# cap_meter.net
KiCad netlist of a schematic drawn in EAGLE
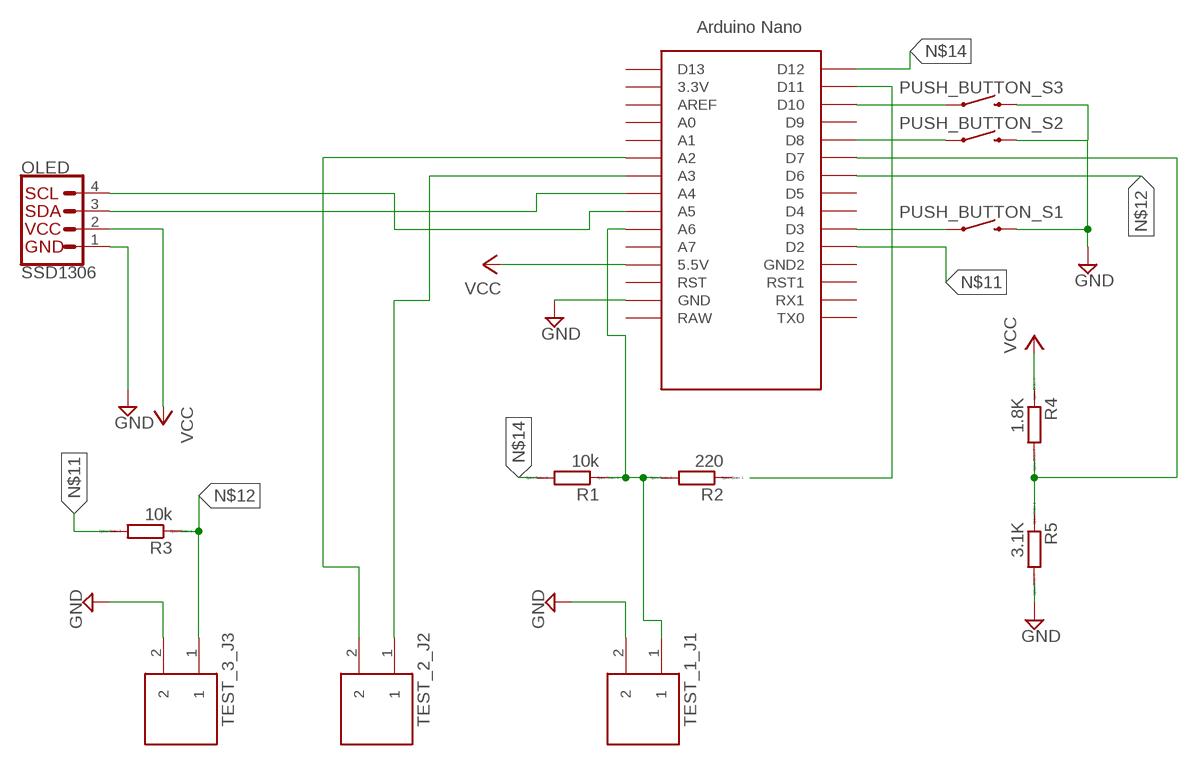
[diagram p0: schematic, sheet 1]

(export (version "E")
  (design (tool "Eeschema 10.0.6"))
  (components
    (comp (ref "OLED")
      (value "SSD1306")
      (footprint "eagle-import:1X04")
      (libsource (lib "eagle-import") (part "I2C_STANDARD"))
    )
    (comp (ref "PUSH_BUTTON_S1")
      (value "MOMENTARY-SWITCH-SPST-PTH-6.0MM-KIT")
      (footprint "eagle-import:TACTILE_SWITCH_PTH_6.0MM_KIT")
      (libsource (lib "eagle-import") (part "MOMENTARY-SWITCH-SPST-PTH-6.0MM-KIT"))
    )
    (comp (ref "PUSH_BUTTON_S2")
      (value "MOMENTARY-SWITCH-SPST-PTH-6.0MM-KIT")
      (footprint "eagle-import:TACTILE_SWITCH_PTH_6.0MM_KIT")
      (libsource (lib "eagle-import") (part "MOMENTARY-SWITCH-SPST-PTH-6.0MM-KIT"))
    )
    (comp (ref "PUSH_BUTTON_S3")
      (value "MOMENTARY-SWITCH-SPST-PTH-6.0MM-KIT")
      (footprint "eagle-import:TACTILE_SWITCH_PTH_6.0MM_KIT")
      (libsource (lib "eagle-import") (part "MOMENTARY-SWITCH-SPST-PTH-6.0MM-KIT"))
    )
    (comp (ref "R1")
      (value "10k")
      (footprint "eagle-import:R1210")
      (libsource (lib "eagle-import") (part "RR1210"))
    )
    (comp (ref "R2")
      (value "220")
      (footprint "eagle-import:R1210")
      (libsource (lib "eagle-import") (part "RR1210"))
    )
    (comp (ref "R3")
      (value "10k")
      (footprint "eagle-import:R1210")
      (libsource (lib "eagle-import") (part "RR1210"))
    )
    (comp (ref "R4")
      (value "1.8K")
      (footprint "eagle-import:R1210")
      (libsource (lib "eagle-import") (part "RR1210"))
    )
    (comp (ref "R5")
      (value "3.1K")
      (footprint "eagle-import:R1210")
      (libsource (lib "eagle-import") (part "RR1210"))
    )
    (comp (ref "TEST_1_J1")
      (value "ED555/2DS")
      (footprint "eagle-import:ED555_2DS")
      (libsource (lib "eagle-import") (part "ED555/2DS"))
    )
    (comp (ref "TEST_2_J2")
      (value "ED555/2DS")
      (footprint "eagle-import:ED555_2DS")
      (libsource (lib "eagle-import") (part "ED555/2DS"))
    )
    (comp (ref "TEST_3_J3")
      (value "ED555/2DS")
      (footprint "eagle-import:ED555_2DS")
      (libsource (lib "eagle-import") (part "ED555/2DS"))
    )
    (comp (ref "U$1")
      (value "NANO")
      (footprint "eagle-import:NANO")
      (libsource (lib "eagle-import") (part "NANO"))
    )
  )
  (nets
    (net (code "1") (name "GND") (class "Default")
      (node (ref "OLED") (pin "1") (pinfunction "1_1") (pintype "power_in"))
      (node (ref "PUSH_BUTTON_S1") (pin "3") (pinfunction "2_3") (pintype "passive"))
      (node (ref "PUSH_BUTTON_S2") (pin "3") (pinfunction "2_3") (pintype "passive"))
      (node (ref "PUSH_BUTTON_S3") (pin "3") (pinfunction "2_3") (pintype "passive"))
      (node (ref "R5") (pin "2") (pinfunction "2_2") (pintype "passive"))
      (node (ref "TEST_1_J1") (pin "2") (pinfunction "2_2") (pintype "bidirectional"))
      (node (ref "TEST_3_J3") (pin "2") (pinfunction "2_2") (pintype "bidirectional"))
      (node (ref "U$1") (pin "GND") (pinfunction "GND_GND") (pintype "bidirectional"))
    )
    (net (code "2") (name "N$11") (class "Default")
      (node (ref "R3") (pin "2") (pinfunction "2_2") (pintype "passive"))
      (node (ref "U$1") (pin "D2") (pinfunction "D2_D2") (pintype "bidirectional"))
    )
    (net (code "3") (name "N$12") (class "Default")
      (node (ref "R3") (pin "1") (pinfunction "1_1") (pintype "passive"))
      (node (ref "TEST_3_J3") (pin "1") (pinfunction "1_1") (pintype "bidirectional"))
      (node (ref "U$1") (pin "D6") (pinfunction "D6_D6") (pintype "bidirectional"))
    )
    (net (code "4") (name "N$14") (class "Default")
      (node (ref "R1") (pin "2") (pinfunction "2_2") (pintype "passive"))
      (node (ref "U$1") (pin "D12") (pinfunction "D12_D12") (pintype "bidirectional"))
    )
    (net (code "5") (name "Net-(OLED-Pad3)") (class "Default")
      (node (ref "OLED") (pin "3") (pinfunction "3_3") (pintype "passive"))
      (node (ref "U$1") (pin "A4") (pinfunction "A4_A4") (pintype "bidirectional"))
    )
    (net (code "6") (name "Net-(OLED-Pad4)") (class "Default")
      (node (ref "OLED") (pin "4") (pinfunction "4_4") (pintype "passive"))
      (node (ref "U$1") (pin "A5") (pinfunction "A5_A5") (pintype "bidirectional"))
    )
    (net (code "7") (name "Net-(PUSH_BUTTON_S1-Pad1)") (class "Default")
      (node (ref "PUSH_BUTTON_S1") (pin "1") (pinfunction "1_1") (pintype "passive"))
      (node (ref "U$1") (pin "D3") (pinfunction "D3_D3") (pintype "bidirectional"))
    )
    (net (code "8") (name "Net-(PUSH_BUTTON_S2-Pad1)") (class "Default")
      (node (ref "PUSH_BUTTON_S2") (pin "1") (pinfunction "1_1") (pintype "passive"))
      (node (ref "U$1") (pin "D8") (pinfunction "D8_D8") (pintype "bidirectional"))
    )
    (net (code "9") (name "Net-(PUSH_BUTTON_S3-Pad1)") (class "Default")
      (node (ref "PUSH_BUTTON_S3") (pin "1") (pinfunction "1_1") (pintype "passive"))
      (node (ref "U$1") (pin "D10") (pinfunction "D10_D10") (pintype "bidirectional"))
    )
    (net (code "10") (name "Net-(R1-Pad1)") (class "Default")
      (node (ref "R1") (pin "1") (pinfunction "1_1") (pintype "passive"))
      (node (ref "R2") (pin "2") (pinfunction "2_2") (pintype "passive"))
      (node (ref "TEST_1_J1") (pin "1") (pinfunction "1_1") (pintype "bidirectional"))
      (node (ref "U$1") (pin "A6") (pinfunction "A6_A6") (pintype "bidirectional"))
    )
    (net (code "11") (name "Net-(R4-Pad2)") (class "Default")
      (node (ref "R4") (pin "2") (pinfunction "2_2") (pintype "passive"))
      (node (ref "R5") (pin "1") (pinfunction "1_1") (pintype "passive"))
      (node (ref "U$1") (pin "D7") (pinfunction "D7_D7") (pintype "bidirectional"))
    )
    (net (code "12") (name "Net-(TEST_2_J2-Pad1)") (class "Default")
      (node (ref "TEST_2_J2") (pin "1") (pinfunction "1_1") (pintype "bidirectional"))
      (node (ref "U$1") (pin "A3") (pinfunction "A3_A3") (pintype "bidirectional"))
    )
    (net (code "13") (name "Net-(TEST_2_J2-Pad2)") (class "Default")
      (node (ref "TEST_2_J2") (pin "2") (pinfunction "2_2") (pintype "bidirectional"))
      (node (ref "U$1") (pin "A2") (pinfunction "A2_A2") (pintype "bidirectional"))
    )
    (net (code "14") (name "VCC") (class "Default")
      (node (ref "OLED") (pin "2") (pinfunction "2_2") (pintype "power_in"))
      (node (ref "R4") (pin "1") (pinfunction "1_1") (pintype "passive"))
      (node (ref "U$1") (pin "5V") (pinfunction "5.5V_5V") (pintype "bidirectional"))
    )
    (net (code "15") (name "unconnected-(R2-Pad1)") (class "Default")
      (node (ref "R2") (pin "1") (pinfunction "1_1") (pintype "passive"))
    )
    (net (code "16") (name "unconnected-(U$1-GND2-PadGND1)") (class "Default")
      (node (ref "U$1") (pin "GND1") (pinfunction "GND2_GND1") (pintype "bidirectional"))
    )
    (net (code "17") (name "unconnected-(U$1-Pad3.3V)") (class "Default")
      (node (ref "U$1") (pin "3.3V") (pinfunction "3.3V_3.3V") (pintype "bidirectional"))
    )
    (net (code "18") (name "unconnected-(U$1-PadA0)") (class "Default")
      (node (ref "U$1") (pin "A0") (pinfunction "A0_A0") (pintype "bidirectional"))
    )
    (net (code "19") (name "unconnected-(U$1-PadA1)") (class "Default")
      (node (ref "U$1") (pin "A1") (pinfunction "A1_A1") (pintype "bidirectional"))
    )
    (net (code "20") (name "unconnected-(U$1-PadA7)") (class "Default")
      (node (ref "U$1") (pin "A7") (pinfunction "A7_A7") (pintype "bidirectional"))
    )
    (net (code "21") (name "unconnected-(U$1-PadAREF)") (class "Default")
      (node (ref "U$1") (pin "AREF") (pinfunction "AREF_AREF") (pintype "bidirectional"))
    )
    (net (code "22") (name "unconnected-(U$1-PadD4)") (class "Default")
      (node (ref "U$1") (pin "D4") (pinfunction "D4_D4") (pintype "bidirectional"))
    )
    (net (code "23") (name "unconnected-(U$1-PadD5)") (class "Default")
      (node (ref "U$1") (pin "D5") (pinfunction "D5_D5") (pintype "bidirectional"))
    )
    (net (code "24") (name "unconnected-(U$1-PadD9)") (class "Default")
      (node (ref "U$1") (pin "D9") (pinfunction "D9_D9") (pintype "bidirectional"))
    )
    (net (code "25") (name "unconnected-(U$1-PadD11)") (class "Default")
      (node (ref "U$1") (pin "D11") (pinfunction "D11_D11") (pintype "bidirectional"))
    )
    (net (code "26") (name "unconnected-(U$1-PadD13)") (class "Default")
      (node (ref "U$1") (pin "D13") (pinfunction "D13_D13") (pintype "bidirectional"))
    )
    (net (code "27") (name "unconnected-(U$1-PadICSP1)") (class "Default")
      (node (ref "U$1") (pin "ICSP1") (pinfunction "ICSP1_ICSP1") (pintype "bidirectional"))
    )
    (net (code "28") (name "unconnected-(U$1-PadICSP2)") (class "Default")
      (node (ref "U$1") (pin "ICSP2") (pinfunction "ICSP2_ICSP2") (pintype "bidirectional"))
    )
    (net (code "29") (name "unconnected-(U$1-PadICSP3)") (class "Default")
      (node (ref "U$1") (pin "ICSP3") (pinfunction "ICSP3_ICSP3") (pintype "bidirectional"))
    )
    (net (code "30") (name "unconnected-(U$1-PadICSP4)") (class "Default")
      (node (ref "U$1") (pin "ICSP4") (pinfunction "ICSP4_ICSP4") (pintype "bidirectional"))
    )
    (net (code "31") (name "unconnected-(U$1-PadICSP5)") (class "Default")
      (node (ref "U$1") (pin "ICSP5") (pinfunction "ICSP5_ICSP5") (pintype "bidirectional"))
    )
    (net (code "32") (name "unconnected-(U$1-PadICSP6)") (class "Default")
      (node (ref "U$1") (pin "ICSP6") (pinfunction "ICSP6_ICSP6") (pintype "bidirectional"))
    )
    (net (code "33") (name "unconnected-(U$1-PadRAW)") (class "Default")
      (node (ref "U$1") (pin "RAW") (pinfunction "RAW_RAW") (pintype "bidirectional"))
    )
    (net (code "34") (name "unconnected-(U$1-PadRST)") (class "Default")
      (node (ref "U$1") (pin "RST") (pinfunction "RST_RST") (pintype "bidirectional"))
    )
    (net (code "35") (name "unconnected-(U$1-PadRST1)") (class "Default")
      (node (ref "U$1") (pin "RST1") (pinfunction "RST1_RST1") (pintype "bidirectional"))
    )
    (net (code "36") (name "unconnected-(U$1-PadRX1)") (class "Default")
      (node (ref "U$1") (pin "RX1") (pinfunction "RX1_RX1") (pintype "bidirectional"))
    )
    (net (code "37") (name "unconnected-(U$1-PadTX0)") (class "Default")
      (node (ref "U$1") (pin "TX0") (pinfunction "TX0_TX0") (pintype "bidirectional"))
    )
  )
)
